# VI_circuit.net
KiCad netlist of a schematic drawn in Altium Designer
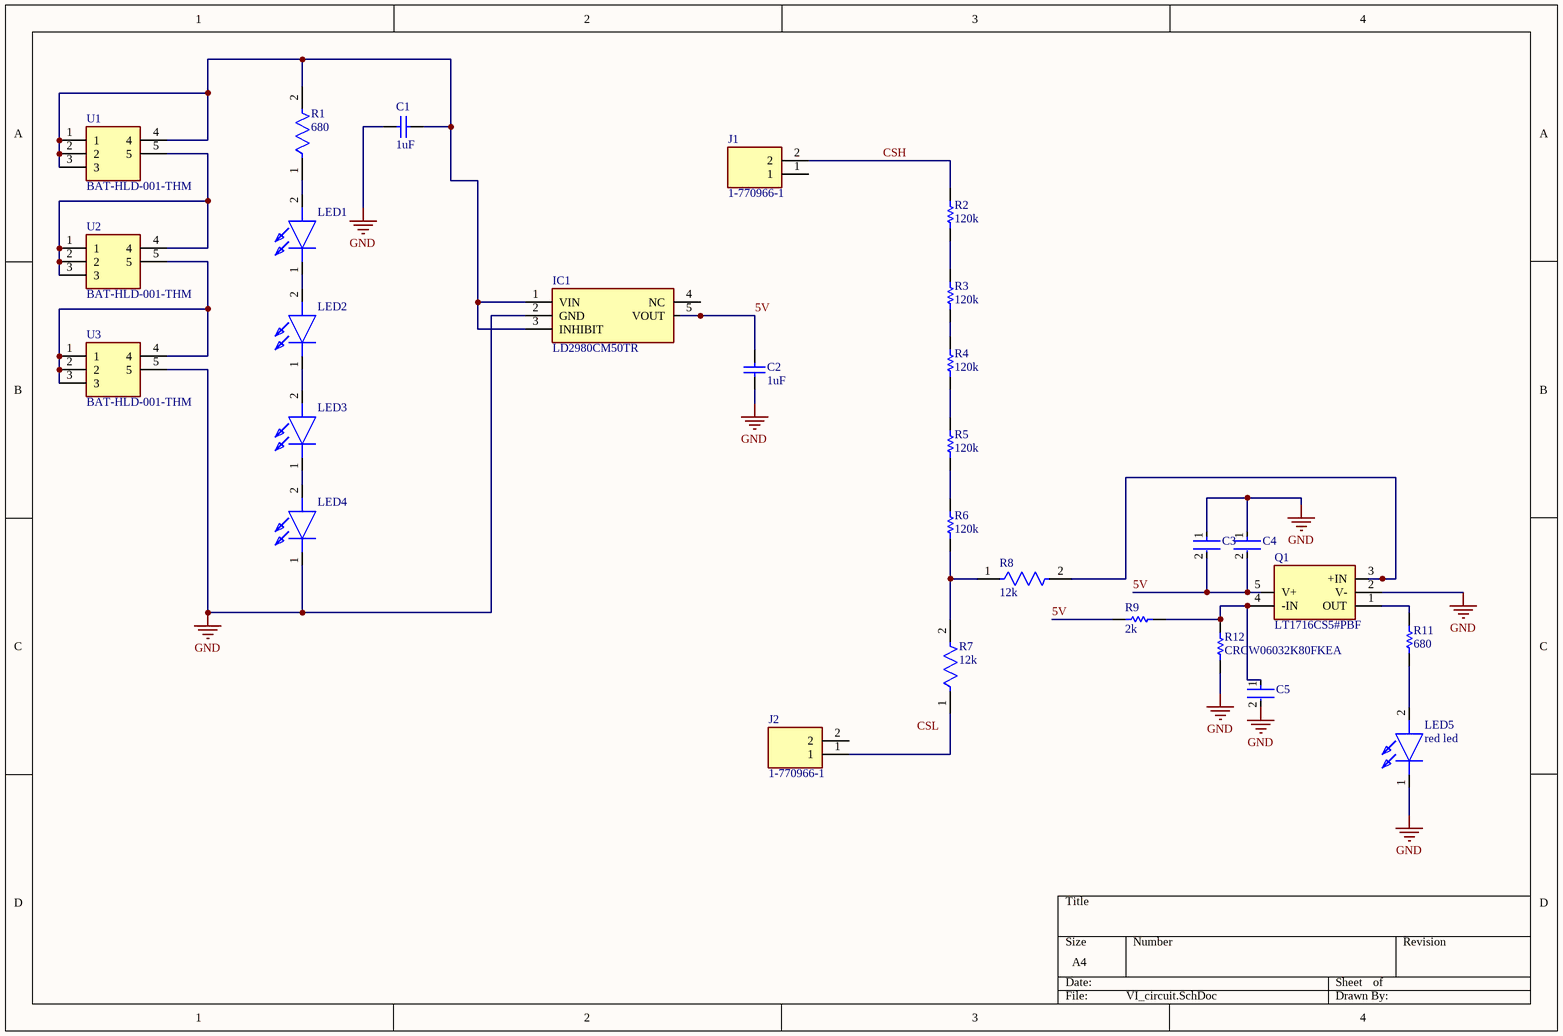
[diagram p0: VI_circuit.SchDoc]

(export (version "E")
  (design (tool "Eeschema 10.0.6"))
  (components
    (comp (ref "C1")
      (value "1uF")
      (footprint "CAPC1608X90X35LL15T15")
      (fields (field (name "MANUFACTURER") "Kemet") (field (name "PART NUMBER") "C0603C105K4RACTU"))
      (libsource (lib "Altium Content Vault") (part "CAP"))
    )
    (comp (ref "C2")
      (value "1uF")
      (footprint "CAPC1608X90X35LL15T15")
      (fields (field (name "MANUFACTURER") "Kemet") (field (name "PART NUMBER") "C0603C105K4RACTU"))
      (libsource (lib "Altium Content Vault") (part "CAP"))
    )
    (comp (ref "C3")
      (value "~")
      (footprint "FP-CGA3E-0_3-0_1-IPC_A")
      (description "Cap Ceramic 100nF 50V X7R 10% Pad SMD 0603 +125°C Automotive T/R")
      (fields (field (name "TOLERANCE") "10%") (field (name "VOLTAGE") "50V"))
      (libsource (lib "Altium Content Vault") (part "b4654b650e69147ec39a6b967a45e02"))
    )
    (comp (ref "C4")
      (value "~")
      (footprint "FP-0603-L_1_6_0_1-W_0_8_0-IPC_A")
      (description "None")
      (fields (field (name "TOLERANCE") "10%"))
      (libsource (lib "Altium Content Vault") (part "02cd4be3c70576c341d710602a673aa"))
    )
    (comp (ref "C5")
      (value "~")
      (footprint "FP-0603-L_1_6_0_1-W_0_8_0-IPC_A")
      (description "None")
      (fields (field (name "TOLERANCE") "10%"))
      (libsource (lib "Altium Content Vault") (part "02cd4be3c70576c341d710602a673aa"))
    )
    (comp (ref "IC1")
      (value "LD2980CM50TR")
      (footprint "SamacSys:SOT95P280X145-5N")
      (description "Integrated Circuit")
      (fields (field (name "MOUSER PART NUMBER") "511-LD2980CM50"))
      (libsource (lib "*") (part "LD2980CM50TR"))
    )
    (comp (ref "J1")
      (value "1-770966-1")
      (footprint "SamacSys:17709661")
      (description "Connector")
      (fields (field (name "MOUSER PART NUMBER") "571-1-770966-1"))
      (libsource (lib "*") (part "1-770966-1"))
    )
    (comp (ref "J2")
      (value "1-770966-1")
      (footprint "SamacSys:17709661")
      (description "Connector")
      (fields (field (name "MOUSER PART NUMBER") "571-1-770966-1"))
      (libsource (lib "*") (part "1-770966-1"))
    )
    (comp (ref "LED1")
      (value "~")
      (footprint "SamacSys:C503B-BCN")
      (description "LED")
      (fields
        (field (name "MANUFACTURER_PART_NUMBER") "C503B-GAS-CB0F0792")
        (field (name "MOUSER PART NUMBER") "941-C503BGASCB0F0792")
      )
      (libsource (lib "*") (part "C503B-GAS-CB0F0792"))
    )
    (comp (ref "LED2")
      (value "~")
      (footprint "SamacSys:C503B-BCN")
      (description "LED")
      (fields
        (field (name "MANUFACTURER_PART_NUMBER") "C503B-GAS-CB0F0792")
        (field (name "MOUSER PART NUMBER") "941-C503BGASCB0F0792")
      )
      (libsource (lib "*") (part "C503B-GAS-CB0F0792"))
    )
    (comp (ref "LED3")
      (value "~")
      (footprint "SamacSys:C503B-BCN")
      (description "LED")
      (fields
        (field (name "MANUFACTURER_PART_NUMBER") "C503B-GAS-CB0F0792")
        (field (name "MOUSER PART NUMBER") "941-C503BGASCB0F0792")
      )
      (libsource (lib "*") (part "C503B-GAS-CB0F0792"))
    )
    (comp (ref "LED4")
      (value "~")
      (footprint "SamacSys:C503B-BCN")
      (description "LED")
      (fields
        (field (name "MANUFACTURER_PART_NUMBER") "C503B-GAS-CB0F0792")
        (field (name "MOUSER PART NUMBER") "941-C503BGASCB0F0792")
      )
      (libsource (lib "*") (part "C503B-GAS-CB0F0792"))
    )
    (comp (ref "LED5")
      (value "red led")
      (footprint "C503B-BCN")
      (description "LED")
      (fields
        (field (name "MANUFACTURER_PART_NUMBER") "C503B-GAS-CB0F0792")
        (field (name "MOUSER PART NUMBER") "941-C503BGASCB0F0792")
      )
      (libsource (lib "vi") (part "C503B-GAS-CB0F0792"))
    )
    (comp (ref "Q1")
      (value "LT1716CS5#PBF")
      (footprint "SOT95P280X100-5N")
      (description "Transistor")
      (fields (field (name "MOUSER PART NUMBER") "584-LT1716CS5#PBF"))
      (libsource (lib "VI") (part "LT1716CS5#PBF"))
    )
    (comp (ref "R1")
      (value "680")
      (footprint "FP-CRCW0603-e3-MFG")
      (description "RES Thick Film, 680Ω, 1%, 0.1W, 100ppm/°C, 0603")
      (fields (field (name "TOLERANCE") "1%"))
      (libsource (lib "Altium Content Vault") (part "1029c3af85768c4190bb7ad29bc67b5"))
    )
    (comp (ref "R2")
      (value "120k")
      (footprint "RESC1609X50X30NL10T20")
      (fields (field (name "MANUFACTURER") "Vishay Dale") (field (name "PART NUMBER") "CRCW0603120KFKEA"))
      (libsource (lib "Altium Content Vault") (part "RES"))
    )
    (comp (ref "R3")
      (value "120k")
      (footprint "RESC1609X50X30NL10T20")
      (fields (field (name "MANUFACTURER") "Vishay Dale") (field (name "PART NUMBER") "CRCW0603120KFKEA"))
      (libsource (lib "Altium Content Vault") (part "RES"))
    )
    (comp (ref "R4")
      (value "120k")
      (footprint "RESC1609X50X30NL10T20")
      (fields (field (name "MANUFACTURER") "Vishay Dale") (field (name "PART NUMBER") "CRCW0603120KFKEA"))
      (libsource (lib "Altium Content Vault") (part "RES"))
    )
    (comp (ref "R5")
      (value "120k")
      (footprint "RESC1609X50X30NL10T20")
      (fields (field (name "MANUFACTURER") "Vishay Dale") (field (name "PART NUMBER") "CRCW0603120KFKEA"))
      (libsource (lib "Altium Content Vault") (part "RES"))
    )
    (comp (ref "R6")
      (value "120k")
      (footprint "RESC1609X50X30NL10T20")
      (fields (field (name "MANUFACTURER") "Vishay Dale") (field (name "PART NUMBER") "CRCW0603120KFKEA"))
      (libsource (lib "Altium Content Vault") (part "RES"))
    )
    (comp (ref "R7")
      (value "12k")
      (footprint "FP-CRCW0603-e3-IPC_A")
      (description "RES Thick Film, 12kΩ, 1%, 0.1W, 100ppm/°C, 0603")
      (fields (field (name "TOLERANCE") "1%"))
      (libsource (lib "Altium Content Vault") (part "1029c3af85768c4190bb7ad29bc67b5"))
    )
    (comp (ref "R8")
      (value "12k")
      (footprint "FP-CRCW0603-e3-IPC_A")
      (description "RES Thick Film, 12kΩ, 1%, 0.1W, 100ppm/°C, 0603")
      (fields (field (name "TOLERANCE") "1%"))
      (libsource (lib "Altium Content Vault") (part "1029c3af85768c4190bb7ad29bc67b5"))
    )
    (comp (ref "R9")
      (value "2k")
      (footprint "RESC1608X55X30ML15T15")
      (fields (field (name "PART NUMBER") "ERJ-3EKF2001V") (field (name "MANUFACTURER") "Panasonic"))
      (libsource (lib "Altium Content Vault") (part "RES"))
    )
    (comp (ref "R11")
      (value "680")
      (footprint "RESC1608X55X30ML15T15")
      (fields (field (name "PART NUMBER") "ERJ-3EKF2001V") (field (name "MANUFACTURER") "Panasonic"))
      (libsource (lib "Altium Content Vault") (part "RES"))
    )
    (comp (ref "R12")
      (value "CRCW06032K80FKEA")
      (footprint "RESC1609X50X30NL10T20")
      (fields (field (name "MANUFACTURER") "Vishay Dale"))
      (libsource (lib "Altium Content Vault") (part "RES"))
    )
    (comp (ref "U1")
      (value "BAT-HLD-001-THM")
      (footprint "SamacSys:BATHLD001THM")
      (description "Undefined or Miscellaneous")
      (libsource (lib "*") (part "BAT-HLD-001-THM"))
    )
    (comp (ref "U2")
      (value "BAT-HLD-001-THM")
      (footprint "SamacSys:BATHLD001THM")
      (description "Undefined or Miscellaneous")
      (libsource (lib "*") (part "BAT-HLD-001-THM"))
    )
    (comp (ref "U3")
      (value "BAT-HLD-001-THM")
      (footprint "SamacSys:BATHLD001THM")
      (description "Undefined or Miscellaneous")
      (libsource (lib "*") (part "BAT-HLD-001-THM"))
    )
  )
  (nets
    (net (code "1") (name "/5V") (class "Default")
      (node (ref "C2") (pin "2") (pinfunction "2_2") (pintype "passive"))
      (node (ref "C3") (pin "2") (pinfunction "2_2") (pintype "passive"))
      (node (ref "C4") (pin "2") (pinfunction "2_2") (pintype "passive"))
      (node (ref "IC1") (pin "5") (pinfunction "VOUT_5") (pintype "passive"))
      (node (ref "Q1") (pin "5") (pinfunction "V+_5") (pintype "passive"))
      (node (ref "R9") (pin "1") (pinfunction "1_1") (pintype "passive"))
    )
    (net (code "2") (name "/CSH") (class "Default")
      (node (ref "J1") (pin "2") (pinfunction "2_2") (pintype "passive"))
      (node (ref "R2") (pin "2") (pinfunction "2_2") (pintype "passive"))
    )
    (net (code "4") (name "GND") (class "Default")
      (node (ref "C1") (pin "1") (pinfunction "1_1") (pintype "passive"))
      (node (ref "C2") (pin "1") (pinfunction "1_1") (pintype "passive"))
      (node (ref "C3") (pin "1") (pinfunction "1_1") (pintype "passive"))
      (node (ref "C4") (pin "1") (pinfunction "1_1") (pintype "passive"))
      (node (ref "C5") (pin "2") (pinfunction "2_2") (pintype "passive"))
      (node (ref "IC1") (pin "2") (pinfunction "GND_2") (pintype "passive"))
      (node (ref "LED4") (pin "1") (pinfunction "K_1") (pintype "passive"))
      (node (ref "LED5") (pin "1") (pinfunction "K_1") (pintype "passive"))
      (node (ref "Q1") (pin "2") (pinfunction "V-_2") (pintype "passive"))
      (node (ref "R12") (pin "1") (pinfunction "1_1") (pintype "passive"))
      (node (ref "U3") (pin "5") (pinfunction "5_5") (pintype "passive"))
    )
    (net (code "5") (name "Net-(IC1-INHIBIT)") (class "Default")
      (node (ref "C1") (pin "2") (pinfunction "2_2") (pintype "passive"))
      (node (ref "IC1") (pin "1") (pinfunction "VIN_1") (pintype "passive"))
      (node (ref "IC1") (pin "3") (pinfunction "INHIBIT_3") (pintype "passive"))
      (node (ref "R1") (pin "2") (pinfunction "2_2") (pintype "passive"))
      (node (ref "U1") (pin "1") (pinfunction "1_1") (pintype "passive"))
      (node (ref "U1") (pin "2") (pinfunction "2_2") (pintype "passive"))
      (node (ref "U1") (pin "3") (pinfunction "3_3") (pintype "passive"))
      (node (ref "U1") (pin "4") (pinfunction "4_4") (pintype "passive"))
    )
    (net (code "6") (name "Net-(J2-Pad1)") (class "Default")
      (node (ref "J2") (pin "1") (pinfunction "1_1") (pintype "passive"))
      (node (ref "R7") (pin "1") (pinfunction "1_1") (pintype "passive"))
    )
    (net (code "7") (name "Net-(LED1-A)") (class "Default")
      (node (ref "LED1") (pin "2") (pinfunction "A_2") (pintype "passive"))
      (node (ref "R1") (pin "1") (pinfunction "1_1") (pintype "passive"))
    )
    (net (code "8") (name "Net-(LED1-K)") (class "Default")
      (node (ref "LED1") (pin "1") (pinfunction "K_1") (pintype "passive"))
      (node (ref "LED2") (pin "2") (pinfunction "A_2") (pintype "passive"))
    )
    (net (code "9") (name "Net-(LED2-K)") (class "Default")
      (node (ref "LED2") (pin "1") (pinfunction "K_1") (pintype "passive"))
      (node (ref "LED3") (pin "2") (pinfunction "A_2") (pintype "passive"))
    )
    (net (code "10") (name "Net-(LED3-K)") (class "Default")
      (node (ref "LED3") (pin "1") (pinfunction "K_1") (pintype "passive"))
      (node (ref "LED4") (pin "2") (pinfunction "A_2") (pintype "passive"))
    )
    (net (code "11") (name "Net-(LED5-A)") (class "Default")
      (node (ref "LED5") (pin "2") (pinfunction "A_2") (pintype "passive"))
      (node (ref "R11") (pin "1") (pinfunction "1_1") (pintype "passive"))
    )
    (net (code "12") (name "Net-(Q1-+IN)") (class "Default")
      (node (ref "Q1") (pin "3") (pinfunction "+IN_3") (pintype "passive"))
      (node (ref "R8") (pin "2") (pinfunction "2_2") (pintype "passive"))
    )
    (net (code "13") (name "Net-(Q1--IN)") (class "Default")
      (node (ref "C5") (pin "1") (pinfunction "1_1") (pintype "passive"))
      (node (ref "Q1") (pin "4") (pinfunction "-IN_4") (pintype "passive"))
      (node (ref "R12") (pin "2") (pinfunction "2_2") (pintype "passive"))
      (node (ref "R9") (pin "2") (pinfunction "2_2") (pintype "passive"))
    )
    (net (code "14") (name "Net-(Q1-OUT)") (class "Default")
      (node (ref "Q1") (pin "1") (pinfunction "OUT_1") (pintype "passive"))
      (node (ref "R11") (pin "2") (pinfunction "2_2") (pintype "passive"))
    )
    (net (code "15") (name "Net-(R2-Pad1)") (class "Default")
      (node (ref "R2") (pin "1") (pinfunction "1_1") (pintype "passive"))
      (node (ref "R3") (pin "2") (pinfunction "2_2") (pintype "passive"))
    )
    (net (code "16") (name "Net-(R3-Pad1)") (class "Default")
      (node (ref "R3") (pin "1") (pinfunction "1_1") (pintype "passive"))
      (node (ref "R4") (pin "2") (pinfunction "2_2") (pintype "passive"))
    )
    (net (code "17") (name "Net-(R4-Pad1)") (class "Default")
      (node (ref "R4") (pin "1") (pinfunction "1_1") (pintype "passive"))
      (node (ref "R5") (pin "2") (pinfunction "2_2") (pintype "passive"))
    )
    (net (code "18") (name "Net-(R5-Pad1)") (class "Default")
      (node (ref "R5") (pin "1") (pinfunction "1_1") (pintype "passive"))
      (node (ref "R6") (pin "2") (pinfunction "2_2") (pintype "passive"))
    )
    (net (code "19") (name "Net-(R6-Pad1)") (class "Default")
      (node (ref "R6") (pin "1") (pinfunction "1_1") (pintype "passive"))
      (node (ref "R7") (pin "2") (pinfunction "2_2") (pintype "passive"))
      (node (ref "R8") (pin "1") (pinfunction "1_1") (pintype "passive"))
    )
    (net (code "20") (name "Net-(U1-Pad5)") (class "Default")
      (node (ref "U1") (pin "5") (pinfunction "5_5") (pintype "passive"))
      (node (ref "U2") (pin "1") (pinfunction "1_1") (pintype "passive"))
      (node (ref "U2") (pin "2") (pinfunction "2_2") (pintype "passive"))
      (node (ref "U2") (pin "3") (pinfunction "3_3") (pintype "passive"))
      (node (ref "U2") (pin "4") (pinfunction "4_4") (pintype "passive"))
    )
    (net (code "21") (name "Net-(U2-Pad5)") (class "Default")
      (node (ref "U2") (pin "5") (pinfunction "5_5") (pintype "passive"))
      (node (ref "U3") (pin "1") (pinfunction "1_1") (pintype "passive"))
      (node (ref "U3") (pin "2") (pinfunction "2_2") (pintype "passive"))
      (node (ref "U3") (pin "3") (pinfunction "3_3") (pintype "passive"))
      (node (ref "U3") (pin "4") (pinfunction "4_4") (pintype "passive"))
    )
    (net (code "22") (name "unconnected-(IC1-NC-Pad4)") (class "Default")
      (node (ref "IC1") (pin "4") (pinfunction "NC_4") (pintype "passive"))
    )
    (net (code "23") (name "unconnected-(J1-Pad1)") (class "Default")
      (node (ref "J1") (pin "1") (pinfunction "1_1") (pintype "passive"))
    )
    (net (code "24") (name "unconnected-(J2-Pad2)") (class "Default")
      (node (ref "J2") (pin "2") (pinfunction "2_2") (pintype "passive"))
    )
  )
)
